# 12V_Input_Circuitry.net
KiCad netlist of a schematic drawn in Altium Designer
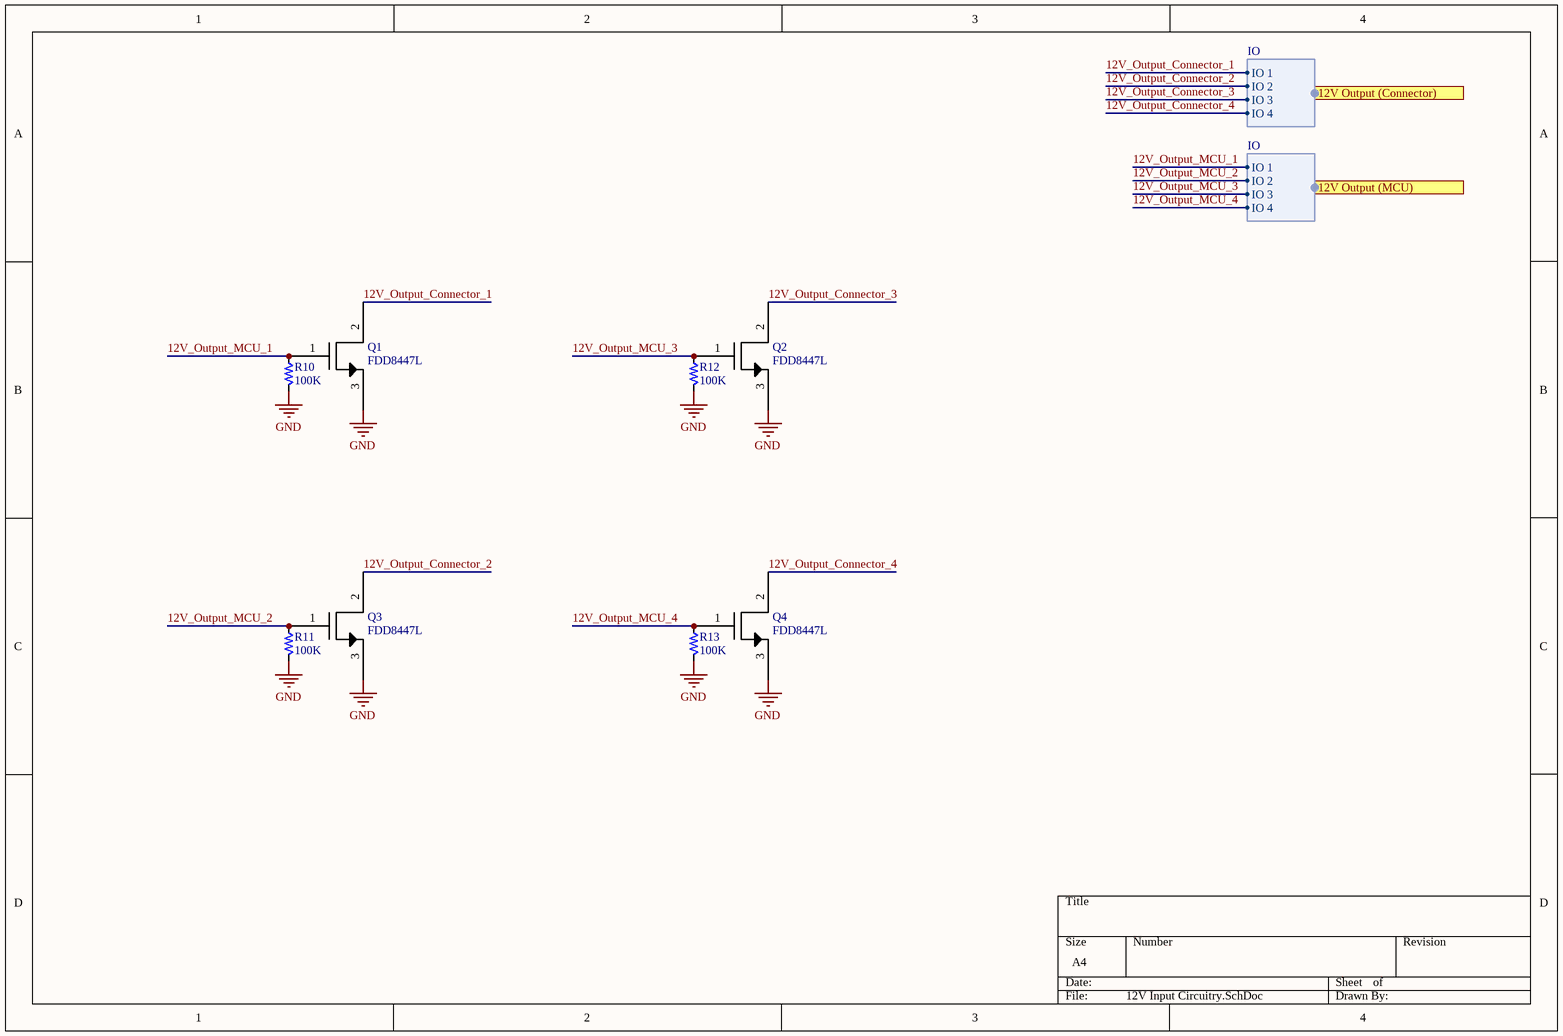
[diagram p0: 12V Input Circuitry.SchDoc]

(export (version "E")
  (design (tool "Eeschema 10.0.6"))
  (components
    (comp (ref "Q1")
      (value "FDD8447L")
      (footprint "FDD8447L")
      (libsource (lib "Fairchild NMOS - DPAK") (part "NMOS"))
    )
    (comp (ref "Q2")
      (value "FDD8447L")
      (footprint "FDD8447L")
      (libsource (lib "Fairchild NMOS - DPAK") (part "NMOS"))
    )
    (comp (ref "Q3")
      (value "FDD8447L")
      (footprint "FDD8447L")
      (libsource (lib "Fairchild NMOS - DPAK") (part "NMOS"))
    )
    (comp (ref "Q4")
      (value "FDD8447L")
      (footprint "FDD8447L")
      (libsource (lib "Fairchild NMOS - DPAK") (part "NMOS"))
    )
    (comp (ref "R10")
      (value "SCH_GENERIC_RESISTOR_0603")
      (footprint "PCB_GENERIC_SMD_0603")
      (description "Generic SMD resistor 0603")
      (fields (field (name "RESISTANCE") "100K"))
      (libsource (lib "SCH_GENERIC_RESISTOR_0603") (part "SCH_GENERIC_RESISTOR_0603"))
    )
    (comp (ref "R11")
      (value "SCH_GENERIC_RESISTOR_0603")
      (footprint "PCB_GENERIC_SMD_0603")
      (description "Generic SMD resistor 0603")
      (fields (field (name "RESISTANCE") "100K"))
      (libsource (lib "SCH_GENERIC_RESISTOR_0603") (part "SCH_GENERIC_RESISTOR_0603"))
    )
    (comp (ref "R12")
      (value "SCH_GENERIC_RESISTOR_0603")
      (footprint "PCB_GENERIC_SMD_0603")
      (description "Generic SMD resistor 0603")
      (fields (field (name "RESISTANCE") "100K"))
      (libsource (lib "SCH_GENERIC_RESISTOR_0603") (part "SCH_GENERIC_RESISTOR_0603"))
    )
    (comp (ref "R13")
      (value "SCH_GENERIC_RESISTOR_0603")
      (footprint "PCB_GENERIC_SMD_0603")
      (description "Generic SMD resistor 0603")
      (fields (field (name "RESISTANCE") "100K"))
      (libsource (lib "SCH_GENERIC_RESISTOR_0603") (part "SCH_GENERIC_RESISTOR_0603"))
    )
  )
  (nets
    (net (code "2") (name "/12V_Output_Connector_1") (class "Default")
      (node (ref "Q1") (pin "2") (pinfunction "2_2") (pintype "passive"))
    )
    (net (code "3") (name "/12V_Output_Connector_2") (class "Default")
      (node (ref "Q3") (pin "2") (pinfunction "2_2") (pintype "passive"))
    )
    (net (code "4") (name "/12V_Output_Connector_3") (class "Default")
      (node (ref "Q2") (pin "2") (pinfunction "2_2") (pintype "passive"))
    )
    (net (code "5") (name "/12V_Output_Connector_4") (class "Default")
      (node (ref "Q4") (pin "2") (pinfunction "2_2") (pintype "passive"))
    )
    (net (code "6") (name "/12V_Output_MCU_1") (class "Default")
      (node (ref "Q1") (pin "1") (pinfunction "1_1") (pintype "passive"))
      (node (ref "R10") (pin "1") (pinfunction "1_1") (pintype "passive"))
    )
    (net (code "7") (name "/12V_Output_MCU_2") (class "Default")
      (node (ref "Q3") (pin "1") (pinfunction "1_1") (pintype "passive"))
      (node (ref "R11") (pin "1") (pinfunction "1_1") (pintype "passive"))
    )
    (net (code "8") (name "/12V_Output_MCU_3") (class "Default")
      (node (ref "Q2") (pin "1") (pinfunction "1_1") (pintype "passive"))
      (node (ref "R12") (pin "1") (pinfunction "1_1") (pintype "passive"))
    )
    (net (code "9") (name "/12V_Output_MCU_4") (class "Default")
      (node (ref "Q4") (pin "1") (pinfunction "1_1") (pintype "passive"))
      (node (ref "R13") (pin "1") (pinfunction "1_1") (pintype "passive"))
    )
    (net (code "11") (name "GND") (class "Default")
      (node (ref "Q1") (pin "3") (pinfunction "3_3") (pintype "passive"))
      (node (ref "Q2") (pin "3") (pinfunction "3_3") (pintype "passive"))
      (node (ref "Q3") (pin "3") (pinfunction "3_3") (pintype "passive"))
      (node (ref "Q4") (pin "3") (pinfunction "3_3") (pintype "passive"))
      (node (ref "R10") (pin "2") (pinfunction "2_2") (pintype "passive"))
      (node (ref "R11") (pin "2") (pinfunction "2_2") (pintype "passive"))
      (node (ref "R12") (pin "2") (pinfunction "2_2") (pintype "passive"))
      (node (ref "R13") (pin "2") (pinfunction "2_2") (pintype "passive"))
    )
  )
)
